# Power_2.net
KiCad netlist of a schematic drawn in Altium Designer
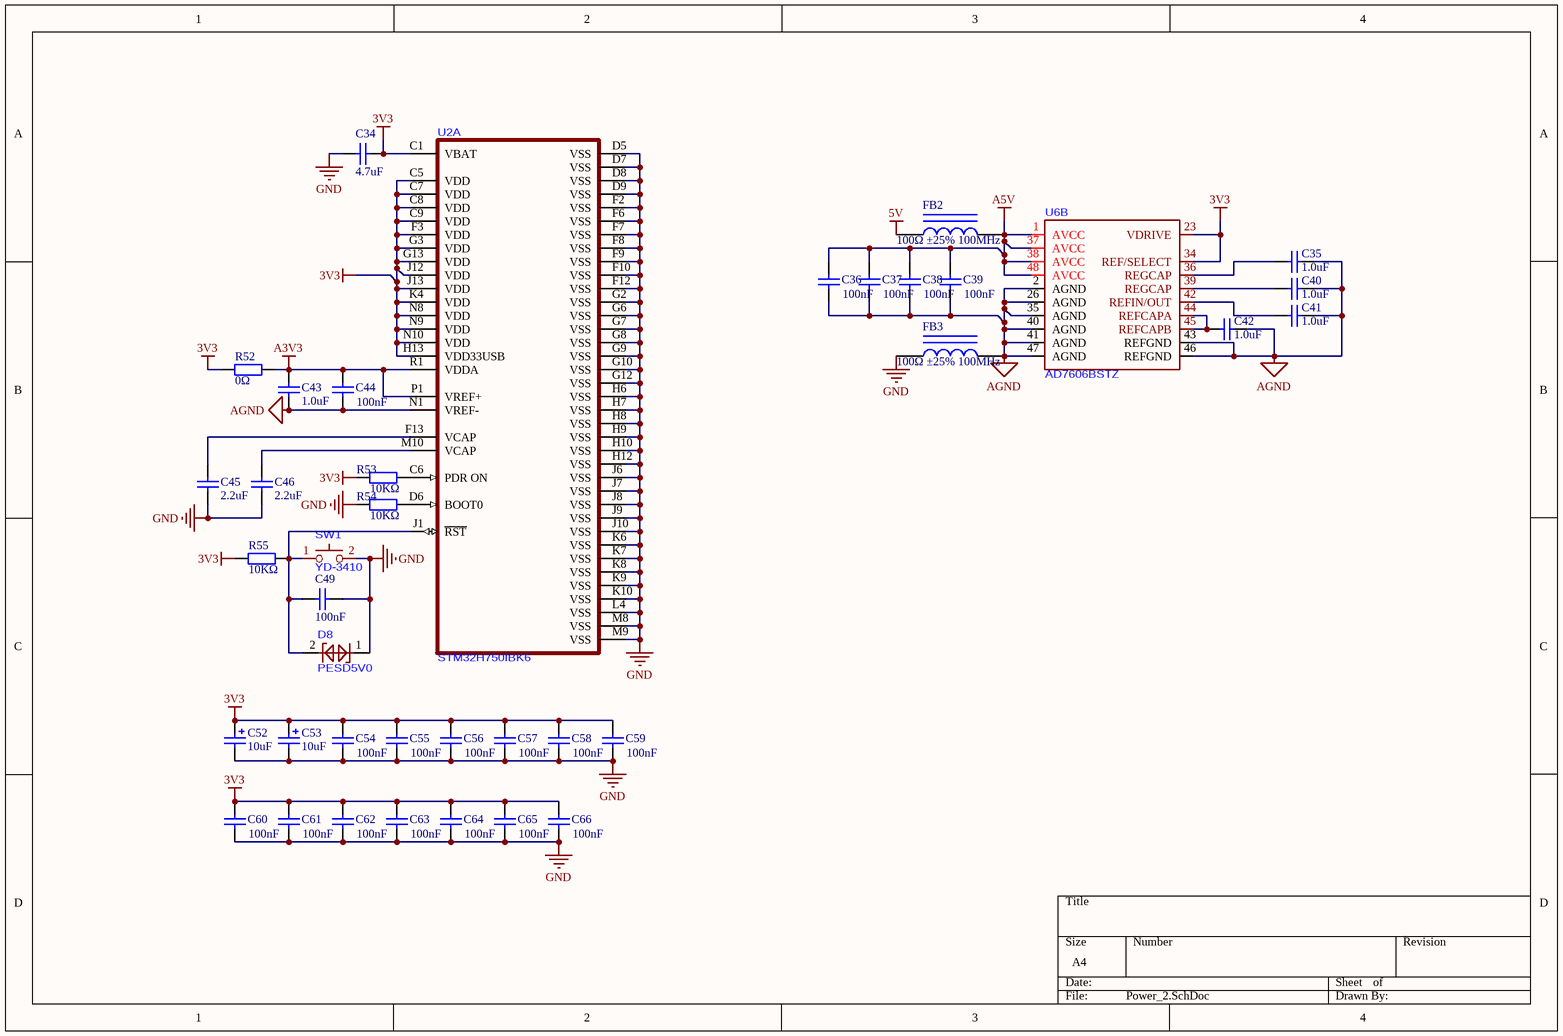
[diagram p0: Power_2.SchDoc]

(export (version "E")
  (design (tool "Eeschema 10.0.6"))
  (components
    (comp (ref "C34")
      (value "4.7uF")
      (footprint "0402_C")
      (description "贴片电容")
      (libsource (lib "Miscellaneous Devices LC") (part "0402 4.7uF (475) 20% 10V"))
    )
    (comp (ref "C35")
      (value "1.0uF")
      (footprint "0402_C")
      (description "贴片电容")
      (libsource (lib "Miscellaneous Devices LC") (part "0402 1.0uF (105) 10% 25V"))
    )
    (comp (ref "C36")
      (value "100nF")
      (footprint "0402_C")
      (description "贴片电容")
      (libsource (lib "Miscellaneous Devices LC") (part "0402 100nF (104) 10% 16V"))
    )
    (comp (ref "C37")
      (value "100nF")
      (footprint "0402_C")
      (description "贴片电容")
      (libsource (lib "Miscellaneous Devices LC") (part "0402 100nF (104) 10% 16V"))
    )
    (comp (ref "C38")
      (value "100nF")
      (footprint "0402_C")
      (description "贴片电容")
      (libsource (lib "Miscellaneous Devices LC") (part "0402 100nF (104) 10% 16V"))
    )
    (comp (ref "C39")
      (value "100nF")
      (footprint "0402_C")
      (description "贴片电容")
      (libsource (lib "Miscellaneous Devices LC") (part "0402 100nF (104) 10% 16V"))
    )
    (comp (ref "C40")
      (value "1.0uF")
      (footprint "0402_C")
      (description "贴片电容")
      (libsource (lib "Miscellaneous Devices LC") (part "0402 1.0uF (105) 10% 25V"))
    )
    (comp (ref "C41")
      (value "1.0uF")
      (footprint "0402_C")
      (description "贴片电容")
      (libsource (lib "Miscellaneous Devices LC") (part "0402 1.0uF (105) 10% 25V"))
    )
    (comp (ref "C42")
      (value "1.0uF")
      (footprint "0402_C")
      (description "贴片电容")
      (libsource (lib "Miscellaneous Devices LC") (part "0402 1.0uF (105) 10% 25V"))
    )
    (comp (ref "C43")
      (value "1.0uF")
      (footprint "0402_C")
      (description "贴片电容")
      (libsource (lib "Miscellaneous Devices LC") (part "0402 1.0uF (105) 10% 25V"))
    )
    (comp (ref "C44")
      (value "100nF")
      (footprint "0402_C")
      (description "贴片电容")
      (libsource (lib "Miscellaneous Devices LC") (part "0402 100nF (104) 10% 16V"))
    )
    (comp (ref "C45")
      (value "2.2uF")
      (footprint "0402_C")
      (description "贴片电容")
      (libsource (lib "Miscellaneous Devices LC") (part "0402 1.0uF (105) 10% 25V"))
    )
    (comp (ref "C46")
      (value "2.2uF")
      (footprint "0402_C")
      (description "贴片电容")
      (libsource (lib "Miscellaneous Devices LC") (part "0402 1.0uF (105) 10% 25V"))
    )
    (comp (ref "C49")
      (value "100nF")
      (footprint "0402_C")
      (description "贴片电容")
      (libsource (lib "Miscellaneous Devices LC") (part "0402 100nF (104) 10% 16V"))
    )
    (comp (ref "C52")
      (value "10uF")
      (footprint "CASE-A_3216")
      (description "钽电容")
      (libsource (lib "Miscellaneous Devices LC") (part "3216 10uF (106) 10% 16V"))
    )
    (comp (ref "C53")
      (value "10uF")
      (footprint "CASE-A_3216")
      (description "钽电容")
      (libsource (lib "Miscellaneous Devices LC") (part "3216 10uF (106) 10% 16V"))
    )
    (comp (ref "C54")
      (value "100nF")
      (footprint "0402_C")
      (description "贴片电容")
      (libsource (lib "Miscellaneous Devices LC") (part "0402 100nF (104) 10% 16V"))
    )
    (comp (ref "C55")
      (value "100nF")
      (footprint "0402_C")
      (description "贴片电容")
      (libsource (lib "Miscellaneous Devices LC") (part "0402 100nF (104) 10% 16V"))
    )
    (comp (ref "C56")
      (value "100nF")
      (footprint "0402_C")
      (description "贴片电容")
      (libsource (lib "Miscellaneous Devices LC") (part "0402 100nF (104) 10% 16V"))
    )
    (comp (ref "C57")
      (value "100nF")
      (footprint "0402_C")
      (description "贴片电容")
      (libsource (lib "Miscellaneous Devices LC") (part "0402 100nF (104) 10% 16V"))
    )
    (comp (ref "C58")
      (value "100nF")
      (footprint "0402_C")
      (description "贴片电容")
      (libsource (lib "Miscellaneous Devices LC") (part "0402 100nF (104) 10% 16V"))
    )
    (comp (ref "C59")
      (value "100nF")
      (footprint "0402_C")
      (description "贴片电容")
      (libsource (lib "Miscellaneous Devices LC") (part "0402 100nF (104) 10% 16V"))
    )
    (comp (ref "C60")
      (value "100nF")
      (footprint "0402_C")
      (description "贴片电容")
      (libsource (lib "Miscellaneous Devices LC") (part "0402 100nF (104) 10% 16V"))
    )
    (comp (ref "C61")
      (value "100nF")
      (footprint "0402_C")
      (description "贴片电容")
      (libsource (lib "Miscellaneous Devices LC") (part "0402 100nF (104) 10% 16V"))
    )
    (comp (ref "C62")
      (value "100nF")
      (footprint "0402_C")
      (description "贴片电容")
      (libsource (lib "Miscellaneous Devices LC") (part "0402 100nF (104) 10% 16V"))
    )
    (comp (ref "C63")
      (value "100nF")
      (footprint "0402_C")
      (description "贴片电容")
      (libsource (lib "Miscellaneous Devices LC") (part "0402 100nF (104) 10% 16V"))
    )
    (comp (ref "C64")
      (value "100nF")
      (footprint "0402_C")
      (description "贴片电容")
      (libsource (lib "Miscellaneous Devices LC") (part "0402 100nF (104) 10% 16V"))
    )
    (comp (ref "C65")
      (value "100nF")
      (footprint "0402_C")
      (description "贴片电容")
      (libsource (lib "Miscellaneous Devices LC") (part "0402 100nF (104) 10% 16V"))
    )
    (comp (ref "C66")
      (value "100nF")
      (footprint "0402_C")
      (description "贴片电容")
      (libsource (lib "Miscellaneous Devices LC") (part "0402 100nF (104) 10% 16V"))
    )
    (comp (ref "D8")
      (value "PESD5V0")
      (footprint "SOD-882_L1.0-W0.6-BI")
      (libsource (lib "JiangCi") (part "PESD5V0F1BL,315"))
    )
    (comp (ref "FB2")
      (value "100Ω ±25% 100MHz")
      (footprint "0805_L")
      (description "贴片磁珠")
      (libsource (lib "Miscellaneous Devices LC") (part "0805 100Ω 25% 100MHz"))
    )
    (comp (ref "FB3")
      (value "100Ω ±25% 100MHz")
      (footprint "0805_L")
      (description "贴片磁珠")
      (libsource (lib "Miscellaneous Devices LC") (part "0805 100Ω 25% 100MHz"))
    )
    (comp (ref "R52")
      (value "0Ω")
      (footprint "0402_R")
      (description "贴片电阻")
      (libsource (lib "Miscellaneous Devices LC") (part "0402 0Ω (0R0) 1%"))
    )
    (comp (ref "R53")
      (value "10KΩ")
      (footprint "0402_R")
      (description "贴片电阻")
      (libsource (lib "Miscellaneous Devices LC") (part "0402 10KΩ (1002) 1%"))
    )
    (comp (ref "R54")
      (value "10KΩ")
      (footprint "0402_R")
      (description "贴片电阻")
      (libsource (lib "Miscellaneous Devices LC") (part "0402 10KΩ (1002) 1%"))
    )
    (comp (ref "R55")
      (value "10KΩ")
      (footprint "0402_R")
      (description "贴片电阻")
      (libsource (lib "") (part "0402 10KΩ (1002) 1%_1"))
    )
    (comp (ref "SW1")
      (value "YD-3410")
      (footprint "SW-SMD_L3.9-W2.9-LS4.8-EH-A")
      (libsource (lib "VeryNB_H750") (part "YD-3410"))
    )
    (comp (ref "U2")
      (value "STM32H750IBK6")
      (footprint "UFBGA176+25")
      (libsource (lib "VeryNB_H750") (part "STM32H750IBK6"))
    )
    (comp (ref "U6")
      (value "AD7606BSTZ")
      (footprint "LQFP-64_L10.0-W10.0-P0.50-LS12.0-TL")
      (libsource (lib "JiangCi") (part "AD7606BSTZ"))
    )
  )
  (nets
    (net (code "1") (name "3V3") (class "Default")
      (node (ref "C34") (pin "2") (pinfunction "2_2") (pintype "passive"))
      (node (ref "C52") (pin "1") (pinfunction "1_1") (pintype "passive"))
      (node (ref "C53") (pin "1") (pinfunction "1_1") (pintype "passive"))
      (node (ref "C54") (pin "2") (pinfunction "2_2") (pintype "passive"))
      (node (ref "C55") (pin "2") (pinfunction "2_2") (pintype "passive"))
      (node (ref "C56") (pin "2") (pinfunction "2_2") (pintype "passive"))
      (node (ref "C57") (pin "2") (pinfunction "2_2") (pintype "passive"))
      (node (ref "C58") (pin "2") (pinfunction "2_2") (pintype "passive"))
      (node (ref "C59") (pin "2") (pinfunction "2_2") (pintype "passive"))
      (node (ref "C60") (pin "2") (pinfunction "2_2") (pintype "passive"))
      (node (ref "C61") (pin "2") (pinfunction "2_2") (pintype "passive"))
      (node (ref "C62") (pin "2") (pinfunction "2_2") (pintype "passive"))
      (node (ref "C63") (pin "2") (pinfunction "2_2") (pintype "passive"))
      (node (ref "C64") (pin "2") (pinfunction "2_2") (pintype "passive"))
      (node (ref "C65") (pin "2") (pinfunction "2_2") (pintype "passive"))
      (node (ref "C66") (pin "2") (pinfunction "2_2") (pintype "passive"))
      (node (ref "R52") (pin "1") (pinfunction "1_1") (pintype "passive"))
      (node (ref "R53") (pin "2") (pinfunction "2_2") (pintype "passive"))
      (node (ref "R55") (pin "1") (pinfunction "1_1") (pintype "passive"))
      (node (ref "U2") (pin "C1") (pinfunction "VBAT_C1") (pintype "power_in"))
      (node (ref "U2") (pin "C5") (pinfunction "VDD_C5") (pintype "power_in"))
      (node (ref "U2") (pin "C7") (pinfunction "VDD_C7") (pintype "power_in"))
      (node (ref "U2") (pin "C8") (pinfunction "VDD_C8") (pintype "power_in"))
      (node (ref "U2") (pin "C9") (pinfunction "VDD_C9") (pintype "power_in"))
      (node (ref "U2") (pin "F3") (pinfunction "VDD_F3") (pintype "power_in"))
      (node (ref "U2") (pin "G13") (pinfunction "VDD_G13") (pintype "power_in"))
      (node (ref "U2") (pin "G3") (pinfunction "VDD_G3") (pintype "power_in"))
      (node (ref "U2") (pin "H13") (pinfunction "VDD33USB_H13") (pintype "power_in"))
      (node (ref "U2") (pin "J12") (pinfunction "VDD_J12") (pintype "power_in"))
      (node (ref "U2") (pin "J13") (pinfunction "VDD_J13") (pintype "power_in"))
      (node (ref "U2") (pin "K4") (pinfunction "VDD_K4") (pintype "power_in"))
      (node (ref "U2") (pin "N10") (pinfunction "VDD_N10") (pintype "power_in"))
      (node (ref "U2") (pin "N8") (pinfunction "VDD_N8") (pintype "power_in"))
      (node (ref "U2") (pin "N9") (pinfunction "VDD_N9") (pintype "power_in"))
      (node (ref "U6") (pin "23") (pinfunction "VDRIVE_23") (pintype "passive"))
      (node (ref "U6") (pin "34") (pinfunction "REF/SELECT_34") (pintype "passive"))
    )
    (net (code "2") (name "5V") (class "Default")
      (node (ref "FB2") (pin "1") (pinfunction "1_1") (pintype "passive"))
    )
    (net (code "3") (name "A3V3") (class "Default")
      (node (ref "C43") (pin "2") (pinfunction "2_2") (pintype "passive"))
      (node (ref "C44") (pin "2") (pinfunction "2_2") (pintype "passive"))
      (node (ref "R52") (pin "2") (pinfunction "2_2") (pintype "passive"))
      (node (ref "U2") (pin "P1") (pinfunction "VREF+_P1") (pintype "power_in"))
      (node (ref "U2") (pin "R1") (pinfunction "VDDA_R1") (pintype "power_in"))
    )
    (net (code "4") (name "A5V") (class "Default")
      (node (ref "C36") (pin "2") (pinfunction "2_2") (pintype "passive"))
      (node (ref "C37") (pin "2") (pinfunction "2_2") (pintype "passive"))
      (node (ref "C38") (pin "2") (pinfunction "2_2") (pintype "passive"))
      (node (ref "C39") (pin "2") (pinfunction "2_2") (pintype "passive"))
      (node (ref "FB2") (pin "2") (pinfunction "2_2") (pintype "passive"))
      (node (ref "U6") (pin "1") (pinfunction "AVCC_1") (pintype "passive"))
      (node (ref "U6") (pin "37") (pinfunction "AVCC_37") (pintype "passive"))
      (node (ref "U6") (pin "38") (pinfunction "AVCC_38") (pintype "passive"))
      (node (ref "U6") (pin "48") (pinfunction "AVCC_48") (pintype "passive"))
    )
    (net (code "5") (name "AGND") (class "Default")
      (node (ref "C35") (pin "1") (pinfunction "1_1") (pintype "passive"))
      (node (ref "C36") (pin "1") (pinfunction "1_1") (pintype "passive"))
      (node (ref "C37") (pin "1") (pinfunction "1_1") (pintype "passive"))
      (node (ref "C38") (pin "1") (pinfunction "1_1") (pintype "passive"))
      (node (ref "C39") (pin "1") (pinfunction "1_1") (pintype "passive"))
      (node (ref "C40") (pin "1") (pinfunction "1_1") (pintype "passive"))
      (node (ref "C41") (pin "1") (pinfunction "1_1") (pintype "passive"))
      (node (ref "C42") (pin "1") (pinfunction "1_1") (pintype "passive"))
      (node (ref "C43") (pin "1") (pinfunction "1_1") (pintype "passive"))
      (node (ref "C44") (pin "1") (pinfunction "1_1") (pintype "passive"))
      (node (ref "FB3") (pin "2") (pinfunction "2_2") (pintype "passive"))
      (node (ref "U2") (pin "N1") (pinfunction "VREF-_N1") (pintype "power_in"))
      (node (ref "U6") (pin "2") (pinfunction "AGND_2") (pintype "passive"))
      (node (ref "U6") (pin "26") (pinfunction "AGND_26") (pintype "passive"))
      (node (ref "U6") (pin "35") (pinfunction "AGND_35") (pintype "passive"))
      (node (ref "U6") (pin "40") (pinfunction "AGND_40") (pintype "passive"))
      (node (ref "U6") (pin "41") (pinfunction "AGND_41") (pintype "passive"))
      (node (ref "U6") (pin "43") (pinfunction "REFGND_43") (pintype "passive"))
      (node (ref "U6") (pin "46") (pinfunction "REFGND_46") (pintype "passive"))
      (node (ref "U6") (pin "47") (pinfunction "AGND_47") (pintype "passive"))
    )
    (net (code "6") (name "GND") (class "Default")
      (node (ref "C34") (pin "1") (pinfunction "1_1") (pintype "passive"))
      (node (ref "C45") (pin "1") (pinfunction "1_1") (pintype "passive"))
      (node (ref "C46") (pin "1") (pinfunction "1_1") (pintype "passive"))
      (node (ref "C49") (pin "1") (pinfunction "1_1") (pintype "passive"))
      (node (ref "C52") (pin "2") (pinfunction "2_2") (pintype "passive"))
      (node (ref "C53") (pin "2") (pinfunction "2_2") (pintype "passive"))
      (node (ref "C54") (pin "1") (pinfunction "1_1") (pintype "passive"))
      (node (ref "C55") (pin "1") (pinfunction "1_1") (pintype "passive"))
      (node (ref "C56") (pin "1") (pinfunction "1_1") (pintype "passive"))
      (node (ref "C57") (pin "1") (pinfunction "1_1") (pintype "passive"))
      (node (ref "C58") (pin "1") (pinfunction "1_1") (pintype "passive"))
      (node (ref "C59") (pin "1") (pinfunction "1_1") (pintype "passive"))
      (node (ref "C60") (pin "1") (pinfunction "1_1") (pintype "passive"))
      (node (ref "C61") (pin "1") (pinfunction "1_1") (pintype "passive"))
      (node (ref "C62") (pin "1") (pinfunction "1_1") (pintype "passive"))
      (node (ref "C63") (pin "1") (pinfunction "1_1") (pintype "passive"))
      (node (ref "C64") (pin "1") (pinfunction "1_1") (pintype "passive"))
      (node (ref "C65") (pin "1") (pinfunction "1_1") (pintype "passive"))
      (node (ref "C66") (pin "1") (pinfunction "1_1") (pintype "passive"))
      (node (ref "D8") (pin "1") (pinfunction "1_1") (pintype "passive"))
      (node (ref "FB3") (pin "1") (pinfunction "1_1") (pintype "passive"))
      (node (ref "R54") (pin "2") (pinfunction "2_2") (pintype "passive"))
      (node (ref "SW1") (pin "2") (pinfunction "2_2") (pintype "passive"))
      (node (ref "U2") (pin "D5") (pinfunction "VSS_D5") (pintype "power_in"))
      (node (ref "U2") (pin "D7") (pinfunction "VSS_D7") (pintype "power_in"))
      (node (ref "U2") (pin "D8") (pinfunction "VSS_D8") (pintype "power_in"))
      (node (ref "U2") (pin "D9") (pinfunction "VSS_D9") (pintype "power_in"))
      (node (ref "U2") (pin "F10") (pinfunction "VSS_F10") (pintype "power_in"))
      (node (ref "U2") (pin "F12") (pinfunction "VSS_F12") (pintype "power_in"))
      (node (ref "U2") (pin "F2") (pinfunction "VSS_F2") (pintype "power_in"))
      (node (ref "U2") (pin "F6") (pinfunction "VSS_F6") (pintype "power_in"))
      (node (ref "U2") (pin "F7") (pinfunction "VSS_F7") (pintype "power_in"))
      (node (ref "U2") (pin "F8") (pinfunction "VSS_F8") (pintype "power_in"))
      (node (ref "U2") (pin "F9") (pinfunction "VSS_F9") (pintype "power_in"))
      (node (ref "U2") (pin "G10") (pinfunction "VSS_G10") (pintype "power_in"))
      (node (ref "U2") (pin "G12") (pinfunction "VSS_G12") (pintype "power_in"))
      (node (ref "U2") (pin "G2") (pinfunction "VSS_G2") (pintype "power_in"))
      (node (ref "U2") (pin "G6") (pinfunction "VSS_G6") (pintype "power_in"))
      (node (ref "U2") (pin "G7") (pinfunction "VSS_G7") (pintype "power_in"))
      (node (ref "U2") (pin "G8") (pinfunction "VSS_G8") (pintype "power_in"))
      (node (ref "U2") (pin "G9") (pinfunction "VSS_G9") (pintype "power_in"))
      (node (ref "U2") (pin "H10") (pinfunction "VSS_H10") (pintype "power_in"))
      (node (ref "U2") (pin "H12") (pinfunction "VSS_H12") (pintype "power_in"))
      (node (ref "U2") (pin "H6") (pinfunction "VSS_H6") (pintype "power_in"))
      (node (ref "U2") (pin "H7") (pinfunction "VSS_H7") (pintype "power_in"))
      (node (ref "U2") (pin "H8") (pinfunction "VSS_H8") (pintype "power_in"))
      (node (ref "U2") (pin "H9") (pinfunction "VSS_H9") (pintype "power_in"))
      (node (ref "U2") (pin "J10") (pinfunction "VSS_J10") (pintype "power_in"))
      (node (ref "U2") (pin "J6") (pinfunction "VSS_J6") (pintype "power_in"))
      (node (ref "U2") (pin "J7") (pinfunction "VSS_J7") (pintype "power_in"))
      (node (ref "U2") (pin "J8") (pinfunction "VSS_J8") (pintype "power_in"))
      (node (ref "U2") (pin "J9") (pinfunction "VSS_J9") (pintype "power_in"))
      (node (ref "U2") (pin "K10") (pinfunction "VSS_K10") (pintype "power_in"))
      (node (ref "U2") (pin "K6") (pinfunction "VSS_K6") (pintype "power_in"))
      (node (ref "U2") (pin "K7") (pinfunction "VSS_K7") (pintype "power_in"))
      (node (ref "U2") (pin "K8") (pinfunction "VSS_K8") (pintype "power_in"))
      (node (ref "U2") (pin "K9") (pinfunction "VSS_K9") (pintype "power_in"))
      (node (ref "U2") (pin "L4") (pinfunction "VSS_L4") (pintype "power_in"))
      (node (ref "U2") (pin "M8") (pinfunction "VSS_M8") (pintype "power_in"))
      (node (ref "U2") (pin "M9") (pinfunction "VSS_M9") (pintype "power_in"))
    )
    (net (code "7") (name "Net-(C35-Pad2)") (class "Default")
      (node (ref "C35") (pin "2") (pinfunction "2_2") (pintype "passive"))
      (node (ref "U6") (pin "36") (pinfunction "REGCAP_36") (pintype "passive"))
    )
    (net (code "8") (name "Net-(C40-Pad2)") (class "Default")
      (node (ref "C40") (pin "2") (pinfunction "2_2") (pintype "passive"))
      (node (ref "U6") (pin "39") (pinfunction "REGCAP_39") (pintype "passive"))
    )
    (net (code "9") (name "Net-(C45-Pad2)") (class "Default")
      (node (ref "C45") (pin "2") (pinfunction "2_2") (pintype "passive"))
      (node (ref "U2") (pin "F13") (pinfunction "VCAP_F13") (pintype "power_in"))
    )
    (net (code "10") (name "Net-(C46-Pad2)") (class "Default")
      (node (ref "C46") (pin "2") (pinfunction "2_2") (pintype "passive"))
      (node (ref "U2") (pin "M10") (pinfunction "VCAP_M10") (pintype "power_in"))
    )
    (net (code "11") (name "Net-(U2A-BOOT0)") (class "Default")
      (node (ref "R54") (pin "1") (pinfunction "1_1") (pintype "passive"))
      (node (ref "U2") (pin "D6") (pinfunction "BOOT0_D6") (pintype "input"))
    )
    (net (code "12") (name "Net-(U2A-PDR_ON)") (class "Default")
      (node (ref "R53") (pin "1") (pinfunction "1_1") (pintype "passive"))
      (node (ref "U2") (pin "C6") (pinfunction "PDR_ON_C6") (pintype "input"))
    )
    (net (code "13") (name "Net-(U2A-~{RST})") (class "Default")
      (node (ref "C49") (pin "2") (pinfunction "2_2") (pintype "passive"))
      (node (ref "D8") (pin "2") (pinfunction "2_2") (pintype "passive"))
      (node (ref "R55") (pin "2") (pinfunction "2_2") (pintype "passive"))
      (node (ref "SW1") (pin "1") (pinfunction "1_1") (pintype "passive"))
      (node (ref "U2") (pin "J1") (pinfunction "~{RST}_J1") (pintype "bidirectional"))
    )
    (net (code "14") (name "Net-(U6B-REFCAPA)") (class "Default")
      (node (ref "C42") (pin "2") (pinfunction "2_2") (pintype "passive"))
      (node (ref "U6") (pin "44") (pinfunction "REFCAPA_44") (pintype "passive"))
      (node (ref "U6") (pin "45") (pinfunction "REFCAPB_45") (pintype "passive"))
    )
    (net (code "15") (name "Net-(U6B-REFIN{slash}OUT)") (class "Default")
      (node (ref "C41") (pin "2") (pinfunction "2_2") (pintype "passive"))
      (node (ref "U6") (pin "42") (pinfunction "REFIN/OUT_42") (pintype "passive"))
    )
  )
)
